# RelayDetect.net
KiCad netlist of a schematic drawn in Altium Designer
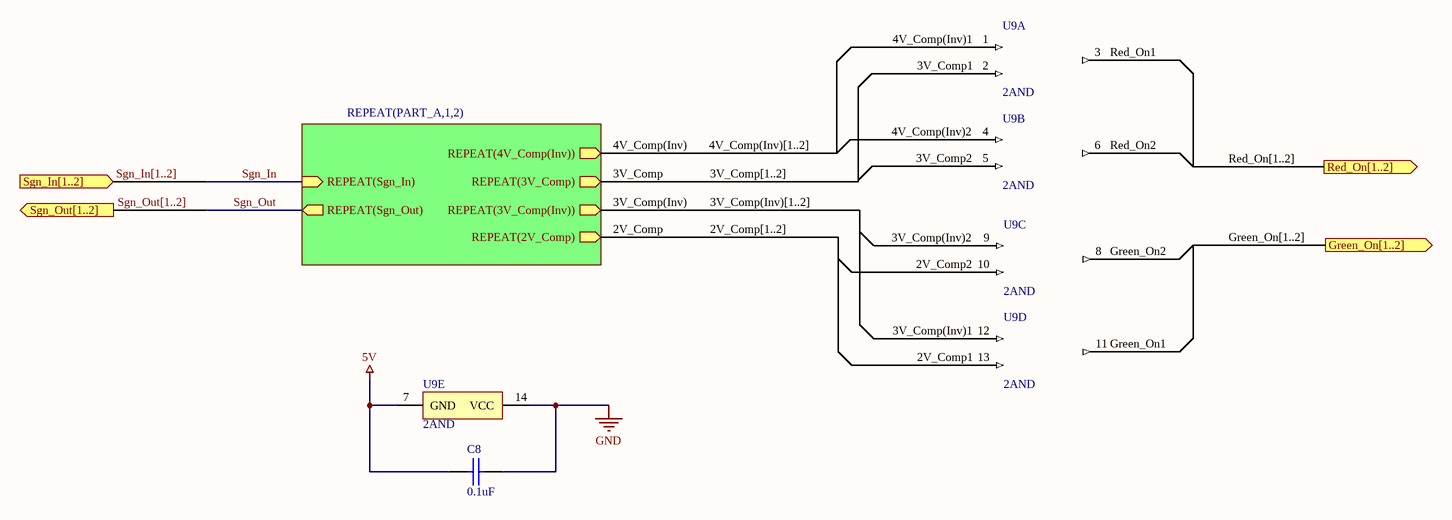
[diagram p0: RelayDetect.SchDoc]

(export (version "E")
  (design (tool "Eeschema 10.0.6"))
  (components
    (comp (ref "C8")
      (value "0.1uF")
      (footprint "0805 Capicator")
      (description "0.1uF X7R 50V 10% 0805")
      (fields
        (field (name "MANUFACTURER") "Murata Manufacturing")
        (field (name "PART NUMBER") "GRM21BR71E104KA01L")
      )
      (libsource (lib "BRT_Components") (part "Cap 0.1uF (0805)"))
    )
    (comp (ref "U9") (value "2AND") (footprint "SOIC-14") (libsource (lib "TSAL") (part "4 (2AND)")))
  )
  (nets
    (net (code "6") (name "/2V_Comp1") (class "Default")
      (node (ref "U9") (pin "13") (pinfunction "B_13") (pintype "input"))
    )
    (net (code "7") (name "/2V_Comp2") (class "Default")
      (node (ref "U9") (pin "10") (pinfunction "B_10") (pintype "input"))
    )
    (net (code "11") (name "/3V_Comp(Inv)1") (class "Default")
      (node (ref "U9") (pin "12") (pinfunction "A_12") (pintype "input"))
    )
    (net (code "12") (name "/3V_Comp(Inv)2") (class "Default")
      (node (ref "U9") (pin "9") (pinfunction "A_9") (pintype "input"))
    )
    (net (code "14") (name "/3V_Comp1") (class "Default")
      (node (ref "U9") (pin "2") (pinfunction "B_2") (pintype "input"))
    )
    (net (code "15") (name "/3V_Comp2") (class "Default")
      (node (ref "U9") (pin "5") (pinfunction "B_5") (pintype "input"))
    )
    (net (code "18") (name "/4V_Comp(Inv)1") (class "Default")
      (node (ref "U9") (pin "1") (pinfunction "A_1") (pintype "input"))
    )
    (net (code "19") (name "/4V_Comp(Inv)2") (class "Default")
      (node (ref "U9") (pin "4") (pinfunction "A_4") (pintype "input"))
    )
    (net (code "21") (name "/Green_On1") (class "Default")
      (node (ref "U9") (pin "11") (pinfunction "Y_11") (pintype "output"))
    )
    (net (code "22") (name "/Green_On2") (class "Default")
      (node (ref "U9") (pin "8") (pinfunction "Y_8") (pintype "output"))
    )
    (net (code "24") (name "/Red_On1") (class "Default")
      (node (ref "U9") (pin "3") (pinfunction "Y_3") (pintype "output"))
    )
    (net (code "25") (name "/Red_On2") (class "Default")
      (node (ref "U9") (pin "6") (pinfunction "Y_6") (pintype "output"))
    )
    (net (code "31") (name "5V") (class "Default")
      (node (ref "C8") (pin "1") (pinfunction "1_1") (pintype "passive"))
      (node (ref "U9") (pin "7") (pinfunction "GND_7") (pintype "passive"))
    )
    (net (code "32") (name "GND") (class "Default")
      (node (ref "C8") (pin "2") (pinfunction "2_2") (pintype "passive"))
      (node (ref "U9") (pin "14") (pinfunction "VCC_14") (pintype "passive"))
    )
  )
)
